# Controller.net
KiCad netlist of a schematic drawn in EAGLE
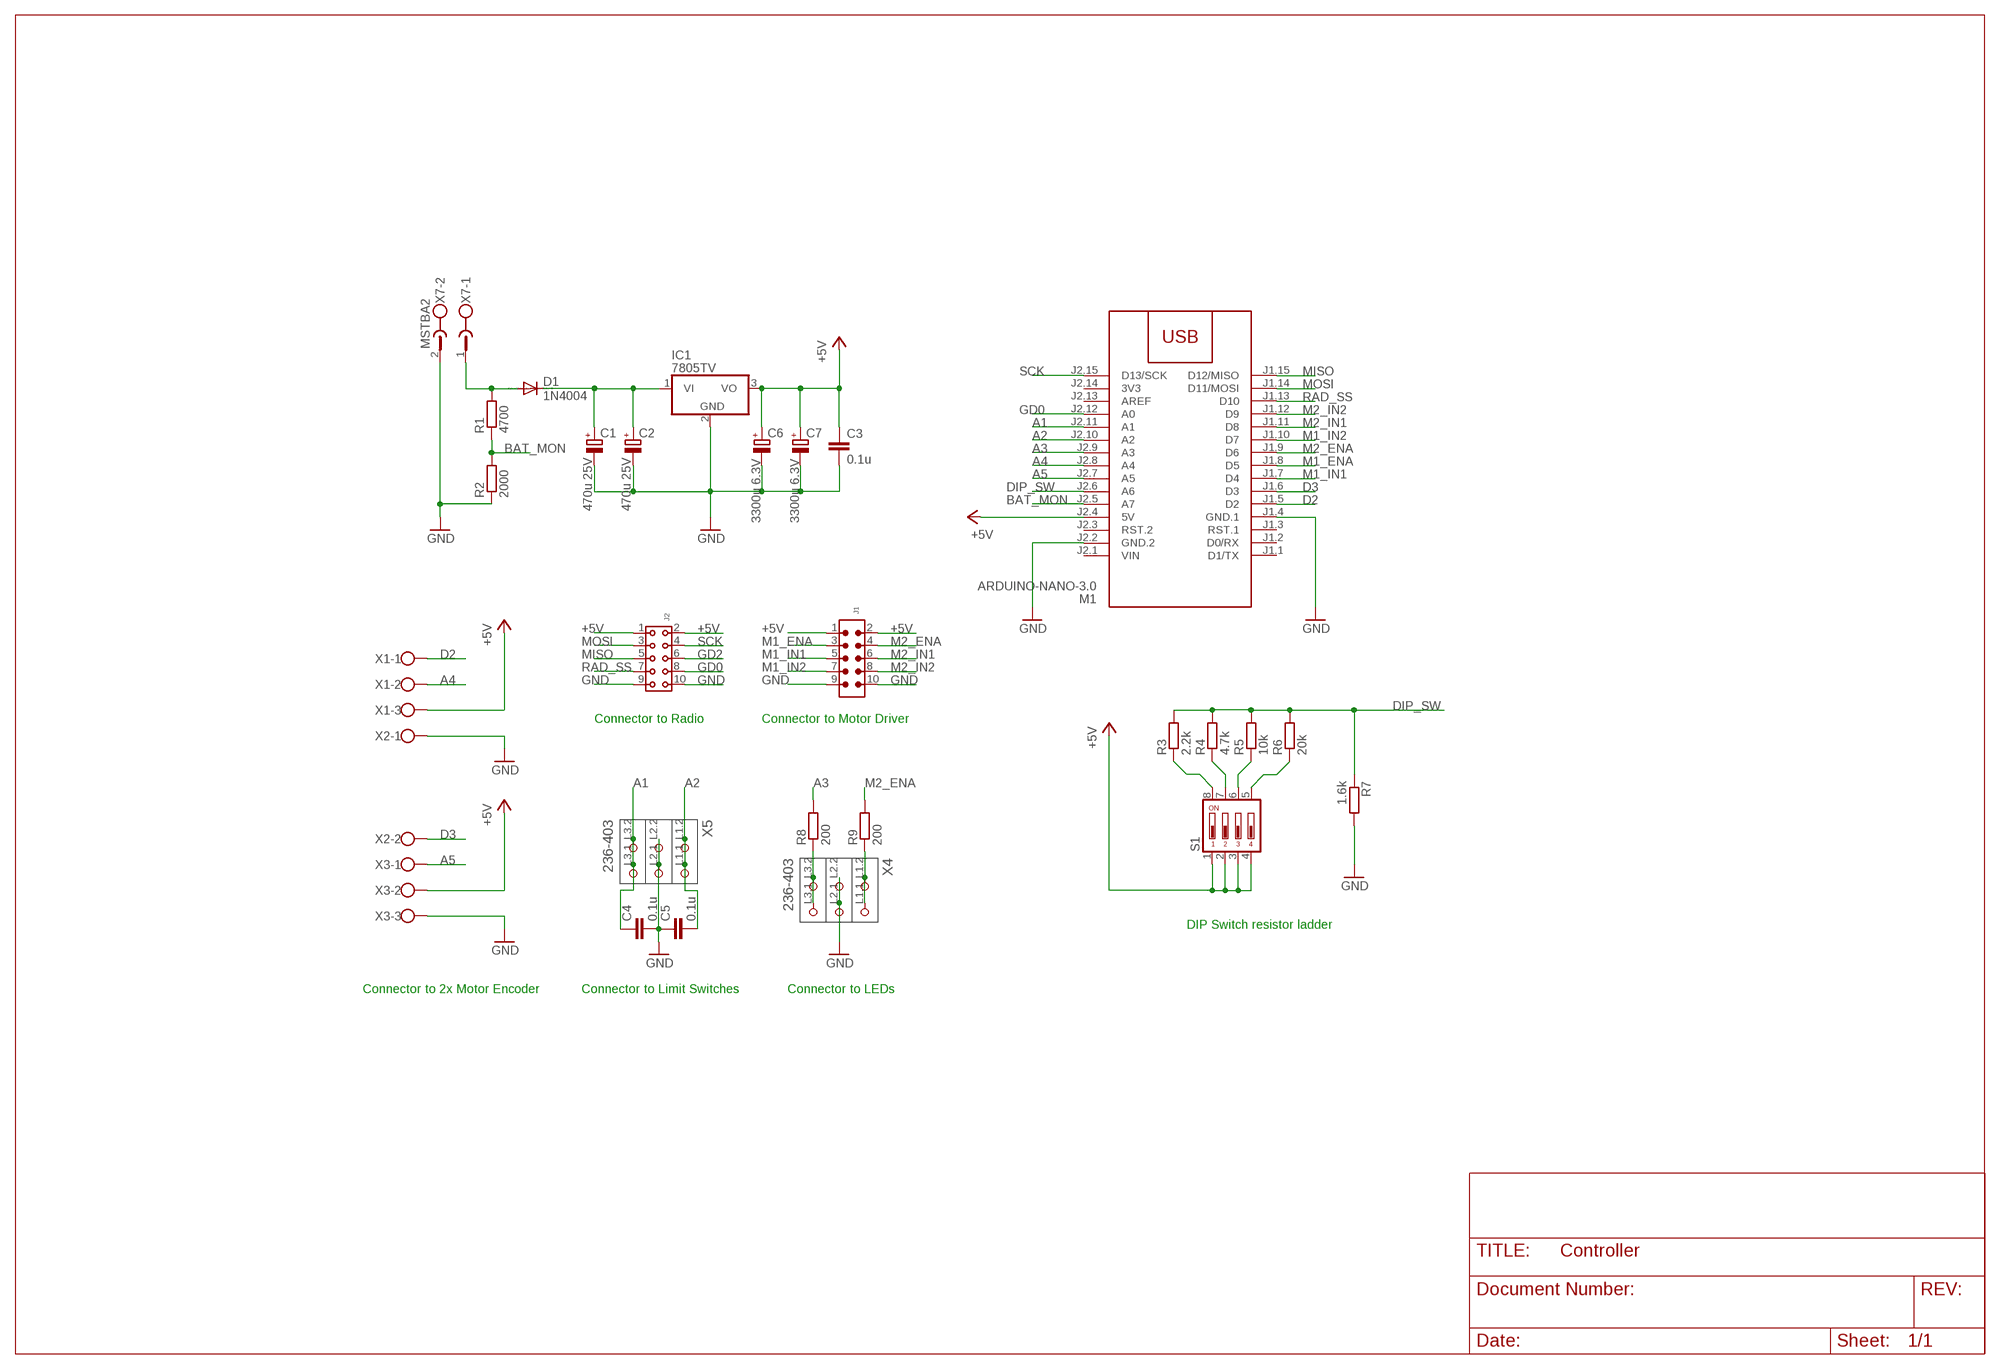
[diagram p0: schematic, sheet 1]

(export (version "E")
  (design (tool "Eeschema 10.0.6"))
  (components
    (comp (ref "C1")
      (value "470u 25V")
      (footprint "eagle-import:E3,5-8")
      (libsource (lib "eagle-import") (part "CPOL-EUE3.5-8"))
    )
    (comp (ref "C2")
      (value "470u 25V")
      (footprint "eagle-import:E3,5-8")
      (libsource (lib "eagle-import") (part "CPOL-EUE3.5-8"))
    )
    (comp (ref "C3")
      (value "0.1u")
      (footprint "eagle-import:C050-030X075")
      (libsource (lib "eagle-import") (part "C-EU050-030X075"))
    )
    (comp (ref "C4")
      (value "0.1u")
      (footprint "eagle-import:C050-030X075")
      (libsource (lib "eagle-import") (part "C-EU050-030X075"))
    )
    (comp (ref "C5")
      (value "0.1u")
      (footprint "eagle-import:C050-030X075")
      (libsource (lib "eagle-import") (part "C-EU050-030X075"))
    )
    (comp (ref "C6")
      (value "3300u 6.3V")
      (footprint "eagle-import:E3,5-10")
      (libsource (lib "eagle-import") (part "CPOL-EUE3.5-10"))
    )
    (comp (ref "C7")
      (value "3300u 6.3V")
      (footprint "eagle-import:E3,5-10")
      (libsource (lib "eagle-import") (part "CPOL-EUE3.5-10"))
    )
    (comp (ref "D1")
      (value "1N4004")
      (footprint "eagle-import:DO41-10")
      (libsource (lib "eagle-import") (part "1N4004"))
    )
    (comp (ref "IC1")
      (value "7805TV")
      (footprint "eagle-import:TO220V")
      (libsource (lib "eagle-import") (part "78TV05"))
    )
    (comp (ref "J1")
      (value "6120XX21621_61201021621")
      (footprint "eagle-import:61201021621")
      (libsource (lib "eagle-import") (part "6120XX21621_61201021621"))
    )
    (comp (ref "J2")
      (value "6130XX21821_61301021821")
      (footprint "eagle-import:61301021821")
      (libsource (lib "eagle-import") (part "6130XX21821_61301021821"))
    )
    (comp (ref "M1")
      (value "ARDUINO-NANO-3.0")
      (footprint "eagle-import:ARDUINO-NANO-3.0")
      (libsource (lib "eagle-import") (part "ARDUINO-NANO-3.0"))
    )
    (comp (ref "R1")
      (value "4700")
      (footprint "eagle-import:0207_10")
      (libsource (lib "eagle-import") (part "R-EU_0207/10"))
    )
    (comp (ref "R2")
      (value "2000")
      (footprint "eagle-import:0207_7")
      (libsource (lib "eagle-import") (part "R-EU_0207/7"))
    )
    (comp (ref "R3")
      (value "2.2k")
      (footprint "eagle-import:0207_10")
      (libsource (lib "eagle-import") (part "R-EU_0207/10"))
    )
    (comp (ref "R4")
      (value "4.7k")
      (footprint "eagle-import:0207_10")
      (libsource (lib "eagle-import") (part "R-EU_0207/10"))
    )
    (comp (ref "R5")
      (value "10k")
      (footprint "eagle-import:0207_10")
      (libsource (lib "eagle-import") (part "R-EU_0207/10"))
    )
    (comp (ref "R6")
      (value "20k")
      (footprint "eagle-import:0207_10")
      (libsource (lib "eagle-import") (part "R-EU_0207/10"))
    )
    (comp (ref "R7")
      (value "1.6k")
      (footprint "eagle-import:0207_10")
      (libsource (lib "eagle-import") (part "R-EU_0207/10"))
    )
    (comp (ref "R8")
      (value "200")
      (footprint "eagle-import:0207_12")
      (libsource (lib "eagle-import") (part "R-EU_0207/12"))
    )
    (comp (ref "R9")
      (value "200")
      (footprint "eagle-import:0207_15")
      (libsource (lib "eagle-import") (part "R-EU_0207/15"))
    )
    (comp (ref "S1")
      (value "DIP04YL")
      (footprint "eagle-import:DIP04YL")
      (libsource (lib "eagle-import") (part "DIP04YL"))
    )
    (comp (ref "X1")
      (value "W237-103")
      (footprint "eagle-import:W237-103")
      (fields (field (name "MPN") "237-103"))
      (libsource (lib "eagle-import") (part "W237-103"))
    )
    (comp (ref "X2")
      (value "W237-102")
      (footprint "eagle-import:W237-102")
      (fields (field (name "MPN") "237-102"))
      (libsource (lib "eagle-import") (part "W237-102"))
    )
    (comp (ref "X3")
      (value "W237-103")
      (footprint "eagle-import:W237-103")
      (fields (field (name "MPN") "237-103"))
      (libsource (lib "eagle-import") (part "W237-103"))
    )
    (comp (ref "X4")
      (value "236-403")
      (footprint "eagle-import:P-236-403")
      (libsource (lib "eagle-import") (part "236-403"))
    )
    (comp (ref "X5")
      (value "236-403")
      (footprint "eagle-import:P-236-403")
      (libsource (lib "eagle-import") (part "236-403"))
    )
    (comp (ref "X7")
      (value "MSTBA2")
      (footprint "eagle-import:MSTBA2")
      (fields (field (name "MF") "FARNELL") (field (name "MPN") "1757242"))
      (libsource (lib "eagle-import") (part "MSTBA2"))
    )
  )
  (nets
    (net (code "1") (name "+5V") (class "Default")
      (node (ref "C3") (pin "1") (pinfunction "1_1") (pintype "passive"))
      (node (ref "C6") (pin "+") (pinfunction "+_+") (pintype "passive"))
      (node (ref "C7") (pin "+") (pinfunction "+_+") (pintype "passive"))
      (node (ref "IC1") (pin "3") (pinfunction "VO_3") (pintype "passive"))
      (node (ref "J1") (pin "1") (pinfunction "1_1") (pintype "passive"))
      (node (ref "J1") (pin "2") (pinfunction "2_2") (pintype "passive"))
      (node (ref "J2") (pin "1") (pinfunction "1_1") (pintype "passive"))
      (node (ref "J2") (pin "2") (pinfunction "2_2") (pintype "passive"))
      (node (ref "M1") (pin "J2.4") (pinfunction "5V_J2.4") (pintype "power_in"))
      (node (ref "S1") (pin "1") (pinfunction "1_1") (pintype "passive"))
      (node (ref "S1") (pin "2") (pinfunction "2_2") (pintype "passive"))
      (node (ref "S1") (pin "3") (pinfunction "3_3") (pintype "passive"))
      (node (ref "S1") (pin "4") (pinfunction "4_4") (pintype "passive"))
      (node (ref "X1") (pin "3") (pinfunction "KL_3") (pintype "passive"))
      (node (ref "X3") (pin "2") (pinfunction "KL_2") (pintype "passive"))
    )
    (net (code "2") (name "/3V3") (class "Default")
      (node (ref "M1") (pin "J2.14") (pinfunction "3V3_J2.14") (pintype "power_in"))
    )
    (net (code "3") (name "/A1") (class "Default")
      (node (ref "C4") (pin "1") (pinfunction "1_1") (pintype "passive"))
      (node (ref "M1") (pin "J2.11") (pinfunction "A1_J2.11") (pintype "bidirectional"))
      (node (ref "X5") (pin "L3.1") (pinfunction "P3.1_L3.1") (pintype "bidirectional"))
      (node (ref "X5") (pin "L3.2") (pinfunction "P3.2_L3.2") (pintype "bidirectional"))
    )
    (net (code "4") (name "/A2") (class "Default")
      (node (ref "C5") (pin "2") (pinfunction "2_2") (pintype "passive"))
      (node (ref "M1") (pin "J2.10") (pinfunction "A2_J2.10") (pintype "bidirectional"))
      (node (ref "X5") (pin "L1.1") (pinfunction "P1.1_L1.1") (pintype "bidirectional"))
      (node (ref "X5") (pin "L1.2") (pinfunction "P1.2_L1.2") (pintype "bidirectional"))
    )
    (net (code "5") (name "/A3") (class "Default")
      (node (ref "M1") (pin "J2.9") (pinfunction "A3_J2.9") (pintype "bidirectional"))
      (node (ref "R8") (pin "2") (pinfunction "2_2") (pintype "passive"))
    )
    (net (code "6") (name "/A4") (class "Default")
      (node (ref "M1") (pin "J2.8") (pinfunction "A4_J2.8") (pintype "bidirectional"))
      (node (ref "X1") (pin "2") (pinfunction "KL_2") (pintype "passive"))
    )
    (net (code "7") (name "/A5") (class "Default")
      (node (ref "M1") (pin "J2.7") (pinfunction "A5_J2.7") (pintype "bidirectional"))
      (node (ref "X3") (pin "1") (pinfunction "KL_1") (pintype "passive"))
    )
    (net (code "8") (name "/BAT_MON") (class "Default")
      (node (ref "M1") (pin "J2.5") (pinfunction "A7_J2.5") (pintype "bidirectional"))
      (node (ref "R1") (pin "1") (pinfunction "1_1") (pintype "passive"))
      (node (ref "R2") (pin "2") (pinfunction "2_2") (pintype "passive"))
    )
    (net (code "9") (name "/D2") (class "Default")
      (node (ref "M1") (pin "J1.5") (pinfunction "D2_J1.5") (pintype "bidirectional"))
      (node (ref "X1") (pin "1") (pinfunction "KL_1") (pintype "passive"))
    )
    (net (code "10") (name "/D3") (class "Default")
      (node (ref "M1") (pin "J1.6") (pinfunction "D3_J1.6") (pintype "bidirectional"))
      (node (ref "X2") (pin "2") (pinfunction "KL_2") (pintype "passive"))
    )
    (net (code "11") (name "/DIP_SW") (class "Default")
      (node (ref "M1") (pin "J2.6") (pinfunction "A6_J2.6") (pintype "bidirectional"))
      (node (ref "R3") (pin "2") (pinfunction "2_2") (pintype "passive"))
      (node (ref "R4") (pin "2") (pinfunction "2_2") (pintype "passive"))
      (node (ref "R5") (pin "2") (pinfunction "2_2") (pintype "passive"))
      (node (ref "R6") (pin "2") (pinfunction "2_2") (pintype "passive"))
      (node (ref "R7") (pin "1") (pinfunction "1_1") (pintype "passive"))
    )
    (net (code "12") (name "/GD0") (class "Default")
      (node (ref "J2") (pin "8") (pinfunction "8_8") (pintype "passive"))
      (node (ref "M1") (pin "J2.12") (pinfunction "A0_J2.12") (pintype "bidirectional"))
    )
    (net (code "13") (name "/GD2") (class "Default")
      (node (ref "J2") (pin "6") (pinfunction "6_6") (pintype "passive"))
    )
    (net (code "14") (name "/M1_ENA") (class "Default")
      (node (ref "J1") (pin "3") (pinfunction "3_3") (pintype "passive"))
      (node (ref "M1") (pin "J1.8") (pinfunction "D5_J1.8") (pintype "bidirectional"))
    )
    (net (code "15") (name "/M1_IN1") (class "Default")
      (node (ref "J1") (pin "5") (pinfunction "5_5") (pintype "passive"))
      (node (ref "M1") (pin "J1.7") (pinfunction "D4_J1.7") (pintype "bidirectional"))
    )
    (net (code "16") (name "/M1_IN2") (class "Default")
      (node (ref "J1") (pin "7") (pinfunction "7_7") (pintype "passive"))
      (node (ref "M1") (pin "J1.10") (pinfunction "D7_J1.10") (pintype "bidirectional"))
    )
    (net (code "17") (name "/M2_ENA") (class "Default")
      (node (ref "J1") (pin "4") (pinfunction "4_4") (pintype "passive"))
      (node (ref "M1") (pin "J1.9") (pinfunction "D6_J1.9") (pintype "bidirectional"))
      (node (ref "R9") (pin "2") (pinfunction "2_2") (pintype "passive"))
    )
    (net (code "18") (name "/M2_IN1") (class "Default")
      (node (ref "J1") (pin "6") (pinfunction "6_6") (pintype "passive"))
      (node (ref "M1") (pin "J1.11") (pinfunction "D8_J1.11") (pintype "bidirectional"))
    )
    (net (code "19") (name "/M2_IN2") (class "Default")
      (node (ref "J1") (pin "8") (pinfunction "8_8") (pintype "passive"))
      (node (ref "M1") (pin "J1.12") (pinfunction "D9_J1.12") (pintype "bidirectional"))
    )
    (net (code "20") (name "/MISO") (class "Default")
      (node (ref "J2") (pin "5") (pinfunction "5_5") (pintype "passive"))
      (node (ref "M1") (pin "J1.15") (pinfunction "D12/MISO_J1.15") (pintype "bidirectional"))
    )
    (net (code "21") (name "/MOSI") (class "Default")
      (node (ref "J2") (pin "3") (pinfunction "3_3") (pintype "passive"))
      (node (ref "M1") (pin "J1.14") (pinfunction "D11/MOSI_J1.14") (pintype "bidirectional"))
    )
    (net (code "22") (name "/RAD_SS") (class "Default")
      (node (ref "J2") (pin "7") (pinfunction "7_7") (pintype "passive"))
      (node (ref "M1") (pin "J1.13") (pinfunction "D10_J1.13") (pintype "bidirectional"))
    )
    (net (code "23") (name "/SCK") (class "Default")
      (node (ref "J2") (pin "4") (pinfunction "4_4") (pintype "passive"))
      (node (ref "M1") (pin "J2.15") (pinfunction "D13/SCK_J2.15") (pintype "bidirectional"))
    )
    (net (code "24") (name "/VIN") (class "Default")
      (node (ref "M1") (pin "J2.1") (pinfunction "VIN_J2.1") (pintype "power_in"))
    )
    (net (code "25") (name "GND") (class "Default")
      (node (ref "C1") (pin "-") (pinfunction "-_-") (pintype "passive"))
      (node (ref "C2") (pin "-") (pinfunction "-_-") (pintype "passive"))
      (node (ref "C3") (pin "2") (pinfunction "2_2") (pintype "passive"))
      (node (ref "C4") (pin "2") (pinfunction "2_2") (pintype "passive"))
      (node (ref "C5") (pin "1") (pinfunction "1_1") (pintype "passive"))
      (node (ref "C6") (pin "-") (pinfunction "-_-") (pintype "passive"))
      (node (ref "C7") (pin "-") (pinfunction "-_-") (pintype "passive"))
      (node (ref "IC1") (pin "2") (pinfunction "GND_2") (pintype "passive"))
      (node (ref "J1") (pin "10") (pinfunction "10_10") (pintype "passive"))
      (node (ref "J1") (pin "9") (pinfunction "9_9") (pintype "passive"))
      (node (ref "J2") (pin "10") (pinfunction "10_10") (pintype "passive"))
      (node (ref "J2") (pin "9") (pinfunction "9_9") (pintype "passive"))
      (node (ref "M1") (pin "J1.4") (pinfunction "GND.1_J1.4") (pintype "power_in"))
      (node (ref "M1") (pin "J2.2") (pinfunction "GND.2_J2.2") (pintype "power_in"))
      (node (ref "R2") (pin "1") (pinfunction "1_1") (pintype "passive"))
      (node (ref "R7") (pin "2") (pinfunction "2_2") (pintype "passive"))
      (node (ref "X2") (pin "1") (pinfunction "KL_1") (pintype "passive"))
      (node (ref "X3") (pin "3") (pinfunction "KL_3") (pintype "passive"))
      (node (ref "X4") (pin "L2.1") (pinfunction "P2.1_L2.1") (pintype "bidirectional"))
      (node (ref "X4") (pin "L2.2") (pinfunction "P2.2_L2.2") (pintype "bidirectional"))
      (node (ref "X5") (pin "L2.1") (pinfunction "P2.1_L2.1") (pintype "bidirectional"))
      (node (ref "X5") (pin "L2.2") (pinfunction "P2.2_L2.2") (pintype "bidirectional"))
      (node (ref "X7") (pin "2") (pinfunction "1_2") (pintype "passive"))
    )
    (net (code "26") (name "Net-(D1-PadA)") (class "Default")
      (node (ref "D1") (pin "A") (pinfunction "A_A") (pintype "passive"))
      (node (ref "R1") (pin "2") (pinfunction "2_2") (pintype "passive"))
      (node (ref "X7") (pin "1") (pinfunction "1_1") (pintype "passive"))
    )
    (net (code "27") (name "Net-(IC1-VI)") (class "Default")
      (node (ref "C1") (pin "+") (pinfunction "+_+") (pintype "passive"))
      (node (ref "C2") (pin "+") (pinfunction "+_+") (pintype "passive"))
      (node (ref "D1") (pin "C") (pinfunction "C_C") (pintype "passive"))
      (node (ref "IC1") (pin "1") (pinfunction "VI_1") (pintype "input"))
    )
    (net (code "28") (name "Net-(R3-Pad1)") (class "Default")
      (node (ref "R3") (pin "1") (pinfunction "1_1") (pintype "passive"))
      (node (ref "S1") (pin "8") (pinfunction "8_8") (pintype "passive"))
    )
    (net (code "29") (name "Net-(R4-Pad1)") (class "Default")
      (node (ref "R4") (pin "1") (pinfunction "1_1") (pintype "passive"))
      (node (ref "S1") (pin "7") (pinfunction "7_7") (pintype "passive"))
    )
    (net (code "30") (name "Net-(R5-Pad1)") (class "Default")
      (node (ref "R5") (pin "1") (pinfunction "1_1") (pintype "passive"))
      (node (ref "S1") (pin "6") (pinfunction "6_6") (pintype "passive"))
    )
    (net (code "31") (name "Net-(R6-Pad1)") (class "Default")
      (node (ref "R6") (pin "1") (pinfunction "1_1") (pintype "passive"))
      (node (ref "S1") (pin "5") (pinfunction "5_5") (pintype "passive"))
    )
    (net (code "32") (name "Net-(X4-P1.1)") (class "Default")
      (node (ref "R9") (pin "1") (pinfunction "1_1") (pintype "passive"))
      (node (ref "X4") (pin "L1.1") (pinfunction "P1.1_L1.1") (pintype "bidirectional"))
      (node (ref "X4") (pin "L1.2") (pinfunction "P1.2_L1.2") (pintype "bidirectional"))
    )
    (net (code "33") (name "Net-(X4-P3.1)") (class "Default")
      (node (ref "R8") (pin "1") (pinfunction "1_1") (pintype "passive"))
      (node (ref "X4") (pin "L3.1") (pinfunction "P3.1_L3.1") (pintype "bidirectional"))
      (node (ref "X4") (pin "L3.2") (pinfunction "P3.2_L3.2") (pintype "bidirectional"))
    )
    (net (code "34") (name "unconnected-(M1-AREF-PadJ2.13)") (class "Default")
      (node (ref "M1") (pin "J2.13") (pinfunction "AREF_J2.13") (pintype "bidirectional"))
    )
    (net (code "35") (name "unconnected-(M1-D0{slash}RX-PadJ1.2)") (class "Default")
      (node (ref "M1") (pin "J1.2") (pinfunction "D0/RX_J1.2") (pintype "bidirectional"))
    )
    (net (code "36") (name "unconnected-(M1-D1{slash}TX-PadJ1.1)") (class "Default")
      (node (ref "M1") (pin "J1.1") (pinfunction "D1/TX_J1.1") (pintype "bidirectional"))
    )
    (net (code "37") (name "unconnected-(M1-RST.1-PadJ1.3)") (class "Default")
      (node (ref "M1") (pin "J1.3") (pinfunction "RST.1_J1.3") (pintype "bidirectional"))
    )
    (net (code "38") (name "unconnected-(M1-RST.2-PadJ2.3)") (class "Default")
      (node (ref "M1") (pin "J2.3") (pinfunction "RST.2_J2.3") (pintype "bidirectional"))
    )
  )
)
